# XT-009_Gold_Standard.net
KiCad netlist of a schematic drawn in EAGLE
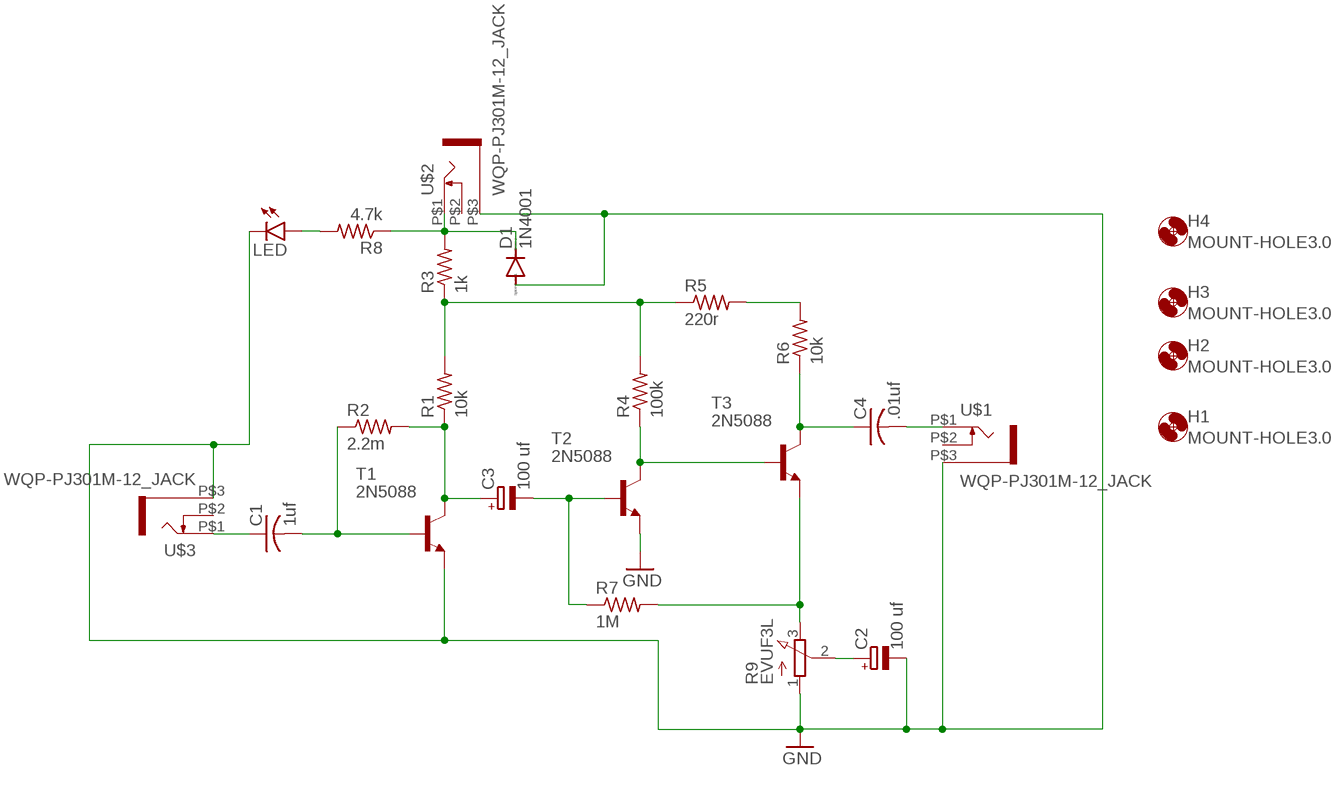
[diagram p0: schematic, sheet 1]

(export (version "E")
  (design (tool "Eeschema 10.0.6"))
  (components
    (comp (ref "C1")
      (value "1uf")
      (footprint "eagle-import:C050-025X075")
      (libsource (lib "eagle-import") (part "C-US050-025X075"))
    )
    (comp (ref "C2")
      (value "100 uf")
      (footprint "eagle-import:E2,5-7")
      (libsource (lib "eagle-import") (part "CPOL-EUE2.5-7"))
    )
    (comp (ref "C3")
      (value "100 uf")
      (footprint "eagle-import:E2,5-7")
      (libsource (lib "eagle-import") (part "CPOL-EUE2.5-7"))
    )
    (comp (ref "C4")
      (value ".01uf")
      (footprint "eagle-import:C050-025X075")
      (libsource (lib "eagle-import") (part "C-US050-025X075"))
    )
    (comp (ref "D1")
      (value "1N4001")
      (footprint "eagle-import:DO41-10")
      (libsource (lib "eagle-import") (part "1N4004"))
    )
    (comp (ref "H1")
      (value "MOUNT-HOLE3.0")
      (footprint "eagle-import:3,0")
      (libsource (lib "eagle-import") (part "MOUNT-HOLE3.0"))
    )
    (comp (ref "H2")
      (value "MOUNT-HOLE3.0")
      (footprint "eagle-import:3,0")
      (libsource (lib "eagle-import") (part "MOUNT-HOLE3.0"))
    )
    (comp (ref "H3")
      (value "MOUNT-HOLE3.0")
      (footprint "eagle-import:3,0")
      (libsource (lib "eagle-import") (part "MOUNT-HOLE3.0"))
    )
    (comp (ref "H4")
      (value "MOUNT-HOLE3.0")
      (footprint "eagle-import:3,0")
      (libsource (lib "eagle-import") (part "MOUNT-HOLE3.0"))
    )
    (comp (ref "LED")
      (value "LED3MM")
      (footprint "eagle-import:LED3MM")
      (libsource (lib "eagle-import") (part "LED3MM"))
    )
    (comp (ref "R1")
      (value "10k")
      (footprint "eagle-import:0207_7")
      (libsource (lib "eagle-import") (part "R-US_0207/7"))
    )
    (comp (ref "R2")
      (value "2.2m")
      (footprint "eagle-import:0207_7")
      (libsource (lib "eagle-import") (part "R-US_0207/7"))
    )
    (comp (ref "R3")
      (value "1k")
      (footprint "eagle-import:0207_7")
      (libsource (lib "eagle-import") (part "R-US_0207/7"))
    )
    (comp (ref "R4")
      (value "100k")
      (footprint "eagle-import:0207_7")
      (libsource (lib "eagle-import") (part "R-US_0207/7"))
    )
    (comp (ref "R5")
      (value "220r")
      (footprint "eagle-import:0207_7")
      (libsource (lib "eagle-import") (part "R-US_0207/7"))
    )
    (comp (ref "R6")
      (value "10k")
      (footprint "eagle-import:0207_7")
      (libsource (lib "eagle-import") (part "rcl_334_R-US_0207/7"))
    )
    (comp (ref "R7")
      (value "1M")
      (footprint "eagle-import:0207_7")
      (libsource (lib "eagle-import") (part "rcl_334_R-US_0207/7"))
    )
    (comp (ref "R8")
      (value "4.7k")
      (footprint "eagle-import:0207_7")
      (libsource (lib "eagle-import") (part "R-US_0207/7"))
    )
    (comp (ref "R9")
      (value "EVUF3L")
      (footprint "eagle-import:EVUFXL")
      (libsource (lib "eagle-import") (part "EVULF3"))
    )
    (comp (ref "T1")
      (value "2N5088")
      (footprint "eagle-import:TO92")
      (libsource (lib "eagle-import") (part "2N5088"))
    )
    (comp (ref "T2")
      (value "2N5088")
      (footprint "eagle-import:TO92")
      (libsource (lib "eagle-import") (part "2N5088"))
    )
    (comp (ref "T3")
      (value "2N5088")
      (footprint "eagle-import:TO92")
      (libsource (lib "eagle-import") (part "transistor_402_2N5088"))
    )
    (comp (ref "U$1")
      (value "WQP-PJ301M-12_JACK")
      (footprint "eagle-import:WQP-PJ301M-12_JACK")
      (libsource (lib "eagle-import") (part "WQP-PJ301M-12_JACK"))
    )
    (comp (ref "U$2")
      (value "WQP-PJ301M-12_JACK")
      (footprint "eagle-import:WQP-PJ301M-12_JACK")
      (libsource (lib "eagle-import") (part "WQP-PJ301M-12_JACK"))
    )
    (comp (ref "U$3")
      (value "WQP-PJ301M-12_JACK")
      (footprint "eagle-import:WQP-PJ301M-12_JACK")
      (libsource (lib "eagle-import") (part "WQP-PJ301M-12_JACK"))
    )
  )
  (nets
    (net (code "1") (name "GND") (class "Default")
      (node (ref "C2") (pin "-") (pinfunction "-_-") (pintype "passive"))
      (node (ref "D1") (pin "A") (pinfunction "A_A") (pintype "passive"))
      (node (ref "LED") (pin "K") (pinfunction "C_K") (pintype "passive"))
      (node (ref "R9") (pin "1") (pinfunction "A_1") (pintype "passive"))
      (node (ref "T1") (pin "3") (pinfunction "E_3") (pintype "passive"))
      (node (ref "T2") (pin "3") (pinfunction "E_3") (pintype "passive"))
      (node (ref "U$1") (pin "P$3") (pinfunction "1_P$3") (pintype "passive"))
      (node (ref "U$2") (pin "P$3") (pinfunction "1_P$3") (pintype "passive"))
      (node (ref "U$3") (pin "P$3") (pinfunction "1_P$3") (pintype "passive"))
    )
    (net (code "2") (name "Net-(LED-PadA)") (class "Default")
      (node (ref "LED") (pin "A") (pinfunction "A_A") (pintype "passive"))
      (node (ref "R8") (pin "2") (pinfunction "2_2") (pintype "passive"))
    )
    (net (code "3") (name "Net-(R1-Pad2)") (class "Default")
      (node (ref "R1") (pin "2") (pinfunction "2_2") (pintype "passive"))
      (node (ref "R3") (pin "1") (pinfunction "1_1") (pintype "passive"))
      (node (ref "R4") (pin "2") (pinfunction "2_2") (pintype "passive"))
      (node (ref "R5") (pin "1") (pinfunction "1_1") (pintype "passive"))
    )
    (net (code "4") (name "Net-(R5-Pad2)") (class "Default")
      (node (ref "R5") (pin "2") (pinfunction "2_2") (pintype "passive"))
      (node (ref "R6") (pin "2") (pinfunction "2_2") (pintype "passive"))
    )
    (net (code "5") (name "Net-(R9-E)") (class "Default")
      (node (ref "R7") (pin "2") (pinfunction "2_2") (pintype "passive"))
      (node (ref "R9") (pin "3") (pinfunction "E_3") (pintype "passive"))
      (node (ref "T3") (pin "3") (pinfunction "E_3") (pintype "passive"))
    )
    (net (code "6") (name "Net-(R9-S)") (class "Default")
      (node (ref "C2") (pin "+") (pinfunction "+_+") (pintype "passive"))
      (node (ref "R9") (pin "2") (pinfunction "S_2") (pintype "passive"))
    )
    (net (code "7") (name "Net-(T1-B)") (class "Default")
      (node (ref "C1") (pin "2") (pinfunction "2_2") (pintype "passive"))
      (node (ref "R2") (pin "1") (pinfunction "1_1") (pintype "passive"))
      (node (ref "T1") (pin "2") (pinfunction "B_2") (pintype "passive"))
    )
    (net (code "8") (name "Net-(T1-C)") (class "Default")
      (node (ref "C3") (pin "+") (pinfunction "+_+") (pintype "passive"))
      (node (ref "R1") (pin "1") (pinfunction "1_1") (pintype "passive"))
      (node (ref "R2") (pin "2") (pinfunction "2_2") (pintype "passive"))
      (node (ref "T1") (pin "1") (pinfunction "C_1") (pintype "passive"))
    )
    (net (code "9") (name "Net-(T2-B)") (class "Default")
      (node (ref "C3") (pin "-") (pinfunction "-_-") (pintype "passive"))
      (node (ref "R7") (pin "1") (pinfunction "1_1") (pintype "passive"))
      (node (ref "T2") (pin "2") (pinfunction "B_2") (pintype "passive"))
    )
    (net (code "10") (name "Net-(T2-C)") (class "Default")
      (node (ref "R4") (pin "1") (pinfunction "1_1") (pintype "passive"))
      (node (ref "T2") (pin "1") (pinfunction "C_1") (pintype "passive"))
      (node (ref "T3") (pin "2") (pinfunction "B_2") (pintype "passive"))
    )
    (net (code "11") (name "Net-(T3-C)") (class "Default")
      (node (ref "C4") (pin "1") (pinfunction "1_1") (pintype "passive"))
      (node (ref "R6") (pin "1") (pinfunction "1_1") (pintype "passive"))
      (node (ref "T3") (pin "1") (pinfunction "C_1") (pintype "passive"))
    )
    (net (code "12") (name "Net-(U$1-2)") (class "Default")
      (node (ref "C4") (pin "2") (pinfunction "2_2") (pintype "passive"))
      (node (ref "U$1") (pin "P$1") (pinfunction "2_P$1") (pintype "passive"))
    )
    (net (code "13") (name "Net-(U$2-2)") (class "Default")
      (node (ref "D1") (pin "C") (pinfunction "C_C") (pintype "passive"))
      (node (ref "R3") (pin "2") (pinfunction "2_2") (pintype "passive"))
      (node (ref "R8") (pin "1") (pinfunction "1_1") (pintype "passive"))
      (node (ref "U$2") (pin "P$1") (pinfunction "2_P$1") (pintype "passive"))
    )
    (net (code "14") (name "Net-(U$3-2)") (class "Default")
      (node (ref "C1") (pin "1") (pinfunction "1_1") (pintype "passive"))
      (node (ref "U$3") (pin "P$1") (pinfunction "2_P$1") (pintype "passive"))
    )
    (net (code "15") (name "unconnected-(U$1-3-PadP$2)") (class "Default")
      (node (ref "U$1") (pin "P$2") (pinfunction "3_P$2") (pintype "passive"))
    )
    (net (code "16") (name "unconnected-(U$2-3-PadP$2)") (class "Default")
      (node (ref "U$2") (pin "P$2") (pinfunction "3_P$2") (pintype "passive"))
    )
    (net (code "17") (name "unconnected-(U$3-3-PadP$2)") (class "Default")
      (node (ref "U$3") (pin "P$2") (pinfunction "3_P$2") (pintype "passive"))
    )
  )
)
